# Anemometro8285.net
KiCad netlist of a schematic drawn in EAGLE
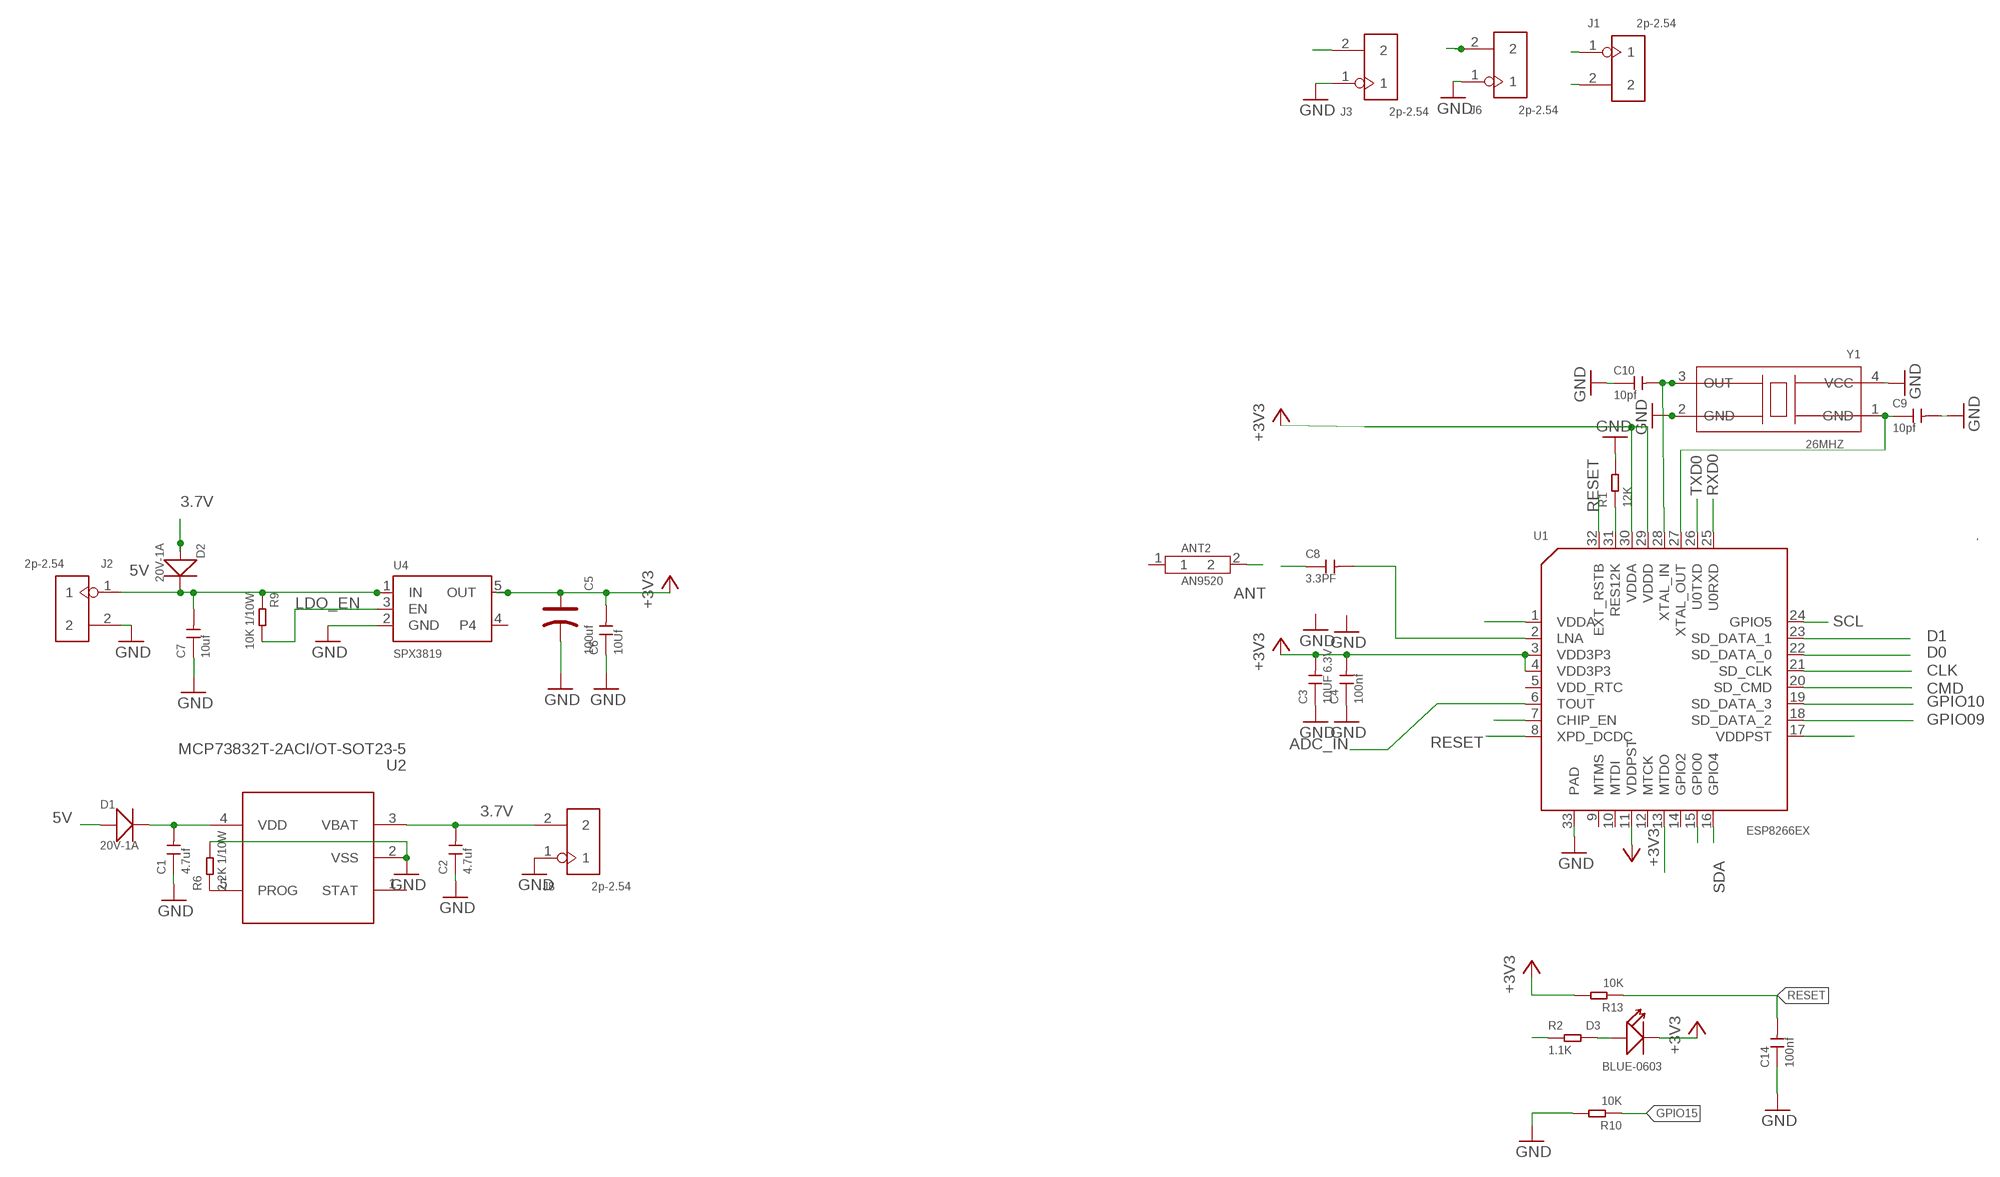
[diagram p0: schematic, sheet 1]

(export (version "E")
  (design (tool "Eeschema 10.0.6"))
  (components
    (comp (ref "ANT2")
      (value "AN9520")
      (footprint "eagle-import:ANT2-SMD-9.5X2X1.2MM")
      (fields (field (name "MPN") "an9520"))
      (libsource (lib "eagle-import") (part "SMD-BUILT-IN-ANTENNA-2.4GHZ(2P-9.5X2.1MM)"))
    )
    (comp (ref "C1")
      (value "4.7uf")
      (footprint "eagle-import:C0603")
      (fields (field (name "MPN") "CC0603KRX5R6BB475"))
      (libsource (lib "eagle-import") (part "CERAMIC-4.7UF-10V-10%-X5R(0603)"))
    )
    (comp (ref "C2")
      (value "4.7uf")
      (footprint "eagle-import:C0603")
      (fields (field (name "MPN") "CC0603KRX5R6BB475"))
      (libsource (lib "eagle-import") (part "CERAMIC-4.7UF-10V-10%-X5R(0603)"))
    )
    (comp (ref "C3")
      (value "10UF 6.3V")
      (footprint "eagle-import:C0603")
      (fields (field (name "MPN") "CC0603MRX5R5BB106"))
      (libsource (lib "eagle-import") (part "CERAMIC-10UF-6.3V-20%-X5R(0603)"))
    )
    (comp (ref "C4")
      (value "100nf")
      (footprint "eagle-import:C0603")
      (fields (field (name "MPN") "CC0603KRX7R9BB104"))
      (libsource (lib "eagle-import") (part "CERAMIC-100NF-50V-10%-X7R(0603)"))
    )
    (comp (ref "C5")
      (value "100uf")
      (footprint "eagle-import:AVX-B")
      (fields (field (name "MPN") "TAJB107M010#NJ"))
      (libsource (lib "eagle-import") (part "TANTALUM-SMD-100UF-10V(AVX-B)"))
    )
    (comp (ref "C6")
      (value "10Uf")
      (footprint "eagle-import:C0603")
      (fields (field (name "MPN") "CC0603KRX7R9BB104"))
      (libsource (lib "eagle-import") (part "CERAMIC-100NF-50V-10%-X7R(0603)"))
    )
    (comp (ref "C7")
      (value "10uf")
      (footprint "eagle-import:C0805")
      (fields (field (name "MPN") "CC0805KKX5R8BB106"))
      (libsource (lib "eagle-import") (part "CERAMIC-10UF-25V-10%-X5R(0805)"))
    )
    (comp (ref "C8")
      (value "3.3PF")
      (footprint "eagle-import:C0603")
      (libsource (lib "eagle-import") (part "CERAMIC-3.3PF-50V-0.25PF-NPO(0603)"))
    )
    (comp (ref "C9")
      (value "10pf")
      (footprint "eagle-import:C0603")
      (libsource (lib "eagle-import") (part "CERAMIC-10PF-50V-5%-NPO(0603)"))
    )
    (comp (ref "C10")
      (value "10pf")
      (footprint "eagle-import:C0603")
      (libsource (lib "eagle-import") (part "CERAMIC-10PF-50V-5%-NPO(0603)"))
    )
    (comp (ref "C14")
      (value "100nf")
      (footprint "eagle-import:C0603")
      (fields (field (name "MPN") "CC0603KRX7R9BB104"))
      (libsource (lib "eagle-import") (part "CERAMIC-100NF-50V-10%-X7R(0603)"))
    )
    (comp (ref "D1")
      (value "20V-1A")
      (footprint "eagle-import:SOD-123")
      (fields (field (name "MPN") "B5819W"))
      (libsource (lib "eagle-import") (part "SMD-DIODE-SCHOTTKY-20V-1A(SOD-123)"))
    )
    (comp (ref "D2")
      (value "20V-1A")
      (footprint "eagle-import:SOD-123")
      (fields (field (name "MPN") "B5819W"))
      (libsource (lib "eagle-import") (part "SMD-DIODE-SCHOTTKY-20V-1A(SOD-123)"))
    )
    (comp (ref "D3")
      (value "BLUE-0603")
      (footprint "eagle-import:LED-0603")
      (fields (field (name "MPN") "19-217-BHC-ZL1M2RY-3T"))
      (libsource (lib "eagle-import") (part "SMD-LED-CLEAR-BLUE(0603)"))
    )
    (comp (ref "J1")
      (value "2p-2.54")
      (footprint "eagle-import:H2-2.54")
      (fields (field (name "MPN") "F185-1102A1BSYA1"))
      (libsource (lib "eagle-import") (part "DIP-BLACK-FEMALE-HEADER-VERT(2P-2.54)"))
    )
    (comp (ref "J2")
      (value "2p-2.54")
      (footprint "eagle-import:H2-2.54")
      (fields (field (name "MPN") "F185-1102A1BSYA1"))
      (libsource (lib "eagle-import") (part "DIP-BLACK-FEMALE-HEADER-VERT(2P-2.54)"))
    )
    (comp (ref "J3")
      (value "2p-2.54")
      (footprint "eagle-import:H2-2.54")
      (fields (field (name "MPN") "P125-1102A0BS116A1"))
      (libsource (lib "eagle-import") (part "DIP-BLACK-MALE-HEADER-VERT(2P-2.54)"))
    )
    (comp (ref "J6")
      (value "2p-2.54")
      (footprint "eagle-import:H2-2.54")
      (fields (field (name "MPN") "P125-1102A0BS116A1"))
      (libsource (lib "eagle-import") (part "DIP-BLACK-MALE-HEADER-VERT(2P-2.54)"))
    )
    (comp (ref "J8")
      (value "2p-2.54")
      (footprint "eagle-import:H2-2.54")
      (fields (field (name "MPN") "F185-1102A1BSYA1"))
      (libsource (lib "eagle-import") (part "DIP-BLACK-FEMALE-HEADER-VERT(2P-2.54)"))
    )
    (comp (ref "R1")
      (value "12K")
      (footprint "eagle-import:R0603")
      (fields (field (name "MPN") "RC0603FR-0712KL"))
      (libsource (lib "eagle-import") (part "SMD-RES-12K-1%-1/10W(0603)"))
    )
    (comp (ref "R2")
      (value "1.1K")
      (footprint "eagle-import:R0603")
      (fields (field (name "MPN") "RC0603JR-071K1L"))
      (libsource (lib "eagle-import") (part "SMD-RES-1.1K-5%-1/10W(0603)"))
    )
    (comp (ref "R6")
      (value "2.2K 1/10W")
      (footprint "eagle-import:R0603")
      (fields (field (name "MPN") "RC0603FR-072K2L"))
      (libsource (lib "eagle-import") (part "SMD-RES-2.2K-1%-1/10W(0603)"))
    )
    (comp (ref "R9")
      (value "10K 1/10W")
      (footprint "eagle-import:R0603")
      (fields (field (name "MPN") "RC0603JR-0710KL"))
      (libsource (lib "eagle-import") (part "SMD-RES-10K-5%-1/10W(0603)"))
    )
    (comp (ref "R10")
      (value "10K")
      (footprint "eagle-import:R0603")
      (fields (field (name "MPN") "RC0603JR-070RL"))
      (libsource (lib "eagle-import") (part "SMD-RES-0R-5%-1/10W(0603)"))
    )
    (comp (ref "R13")
      (value "10K")
      (footprint "eagle-import:R0603")
      (fields (field (name "MPN") "RC0603JR-070RL"))
      (libsource (lib "eagle-import") (part "SMD-RES-0R-5%-1/10W(0603)"))
    )
    (comp (ref "U1")
      (value "ESP8266EX")
      (footprint "eagle-import:QFN32G-0.5-5X5MM")
      (libsource (lib "eagle-import") (part "IC-RF-ESP8266EX(QFN32)"))
    )
    (comp (ref "U2")
      (value "MCP73832T-2ACI/OT-SOT23-5")
      (footprint "eagle-import:SOT-23-5")
      (fields (field (name "MPN") "MCP73832T-2ACI/OT"))
      (libsource (lib "eagle-import") (part "PMIC-MCP73832T-2ACI/OT(SOT23-5)"))
    )
    (comp (ref "U4")
      (value "SPX3819")
      (footprint "eagle-import:SOT23-5")
      (libsource (lib "eagle-import") (part "VREG_SOT23-5"))
    )
    (comp (ref "Y1")
      (value "26MHZ")
      (footprint "eagle-import:X4-SMD-2.5X2.0X0.5MM")
      (fields (field (name "MPN") "7L26002009"))
      (libsource (lib "eagle-import") (part "SMD-CRYSTAL-26MHZ(4P-2.5X2.0X0.8MM)"))
    )
  )
  (nets
    (net (code "1") (name "+3V3") (class "Default")
      (node (ref "C3") (pin "2") (pinfunction "2_2") (pintype "passive"))
      (node (ref "C4") (pin "2") (pinfunction "2_2") (pintype "passive"))
      (node (ref "C5") (pin "+") (pinfunction "+_+") (pintype "passive"))
      (node (ref "C6") (pin "2") (pinfunction "2_2") (pintype "passive"))
      (node (ref "D3") (pin "-") (pinfunction "-_-") (pintype "passive"))
      (node (ref "R13") (pin "2") (pinfunction "2_2") (pintype "passive"))
      (node (ref "U1") (pin "1") (pinfunction "VDDA_1") (pintype "power_in"))
      (node (ref "U1") (pin "11") (pinfunction "VDDPST_11") (pintype "bidirectional"))
      (node (ref "U1") (pin "17") (pinfunction "VDDPST_17") (pintype "bidirectional"))
      (node (ref "U1") (pin "29") (pinfunction "VDDD_29") (pintype "bidirectional"))
      (node (ref "U1") (pin "3") (pinfunction "VDD3P3_3") (pintype "power_in"))
      (node (ref "U1") (pin "30") (pinfunction "VDDA_30") (pintype "bidirectional"))
      (node (ref "U1") (pin "4") (pinfunction "VDD3P3_4") (pintype "power_in"))
      (node (ref "U1") (pin "7") (pinfunction "CHIP_EN_7") (pintype "bidirectional"))
      (node (ref "U4") (pin "5") (pinfunction "OUT_5") (pintype "power_in"))
    )
    (net (code "2") (name "/3.7V") (class "Default")
      (node (ref "C2") (pin "2") (pinfunction "2_2") (pintype "passive"))
      (node (ref "D2") (pin "+") (pinfunction "+_+") (pintype "passive"))
      (node (ref "J8") (pin "2") (pinfunction "2_2") (pintype "bidirectional"))
      (node (ref "U2") (pin "3") (pinfunction "VBAT_3") (pintype "output"))
    )
    (net (code "3") (name "/5V") (class "Default")
      (node (ref "C7") (pin "2") (pinfunction "2_2") (pintype "passive"))
      (node (ref "D1") (pin "+") (pinfunction "+_+") (pintype "passive"))
      (node (ref "D2") (pin "-") (pinfunction "-_-") (pintype "passive"))
      (node (ref "J2") (pin "1") (pinfunction "1_1") (pintype "bidirectional"))
      (node (ref "R9") (pin "1") (pinfunction "1_1") (pintype "passive"))
      (node (ref "U4") (pin "1") (pinfunction "IN_1") (pintype "power_in"))
    )
    (net (code "4") (name "/ADC_IN") (class "Default")
      (node (ref "U1") (pin "6") (pinfunction "TOUT_6") (pintype "output"))
    )
    (net (code "5") (name "/ANT") (class "Default")
      (node (ref "ANT2") (pin "2") (pinfunction "2_2") (pintype "bidirectional"))
      (node (ref "C8") (pin "1") (pinfunction "1_1") (pintype "passive"))
    )
    (net (code "6") (name "/CLK") (class "Default")
      (node (ref "U1") (pin "21") (pinfunction "SD_CLK_21") (pintype "bidirectional"))
    )
    (net (code "7") (name "/CMD") (class "Default")
      (node (ref "U1") (pin "20") (pinfunction "SD_CMD_20") (pintype "bidirectional"))
    )
    (net (code "8") (name "/D0") (class "Default")
      (node (ref "U1") (pin "22") (pinfunction "SD_DATA_0_22") (pintype "bidirectional"))
    )
    (net (code "9") (name "/D1") (class "Default")
      (node (ref "U1") (pin "23") (pinfunction "SD_DATA_1_23") (pintype "bidirectional"))
    )
    (net (code "10") (name "/GPIO0") (class "Default")
      (node (ref "J3") (pin "2") (pinfunction "2_2") (pintype "bidirectional"))
      (node (ref "U1") (pin "15") (pinfunction "GPIO0_15") (pintype "bidirectional"))
    )
    (net (code "11") (name "/GPIO09") (class "Default")
      (node (ref "U1") (pin "18") (pinfunction "SD_DATA_2_18") (pintype "bidirectional"))
    )
    (net (code "12") (name "/GPIO10") (class "Default")
      (node (ref "U1") (pin "19") (pinfunction "SD_DATA_3_19") (pintype "bidirectional"))
    )
    (net (code "13") (name "/LDO_EN") (class "Default")
      (node (ref "R9") (pin "2") (pinfunction "2_2") (pintype "passive"))
      (node (ref "U4") (pin "3") (pinfunction "EN_3") (pintype "input"))
    )
    (net (code "14") (name "/RXD0") (class "Default")
      (node (ref "J1") (pin "2") (pinfunction "2_2") (pintype "bidirectional"))
      (node (ref "U1") (pin "25") (pinfunction "U0RXD_25") (pintype "bidirectional"))
    )
    (net (code "15") (name "/SCL") (class "Default")
      (node (ref "J6") (pin "2") (pinfunction "2_2") (pintype "bidirectional"))
      (node (ref "U1") (pin "24") (pinfunction "GPIO5_24") (pintype "bidirectional"))
    )
    (net (code "16") (name "/SDA") (class "Default")
      (node (ref "U1") (pin "16") (pinfunction "GPIO4_16") (pintype "bidirectional"))
    )
    (net (code "17") (name "/TXD0") (class "Default")
      (node (ref "J1") (pin "1") (pinfunction "1_1") (pintype "bidirectional"))
      (node (ref "R2") (pin "1") (pinfunction "1_1") (pintype "passive"))
      (node (ref "U1") (pin "26") (pinfunction "U0TXD_26") (pintype "bidirectional"))
    )
    (net (code "18") (name "GND") (class "Default")
      (node (ref "C1") (pin "1") (pinfunction "1_1") (pintype "passive"))
      (node (ref "C10") (pin "1") (pinfunction "1_1") (pintype "passive"))
      (node (ref "C14") (pin "1") (pinfunction "1_1") (pintype "passive"))
      (node (ref "C2") (pin "1") (pinfunction "1_1") (pintype "passive"))
      (node (ref "C3") (pin "1") (pinfunction "1_1") (pintype "passive"))
      (node (ref "C4") (pin "1") (pinfunction "1_1") (pintype "passive"))
      (node (ref "C5") (pin "-") (pinfunction "-_-") (pintype "passive"))
      (node (ref "C6") (pin "1") (pinfunction "1_1") (pintype "passive"))
      (node (ref "C7") (pin "1") (pinfunction "1_1") (pintype "passive"))
      (node (ref "C9") (pin "2") (pinfunction "2_2") (pintype "passive"))
      (node (ref "J2") (pin "2") (pinfunction "2_2") (pintype "bidirectional"))
      (node (ref "J3") (pin "1") (pinfunction "1_1") (pintype "bidirectional"))
      (node (ref "J6") (pin "1") (pinfunction "1_1") (pintype "bidirectional"))
      (node (ref "J8") (pin "1") (pinfunction "1_1") (pintype "bidirectional"))
      (node (ref "R1") (pin "2") (pinfunction "2_2") (pintype "passive"))
      (node (ref "R10") (pin "2") (pinfunction "2_2") (pintype "passive"))
      (node (ref "R6") (pin "2") (pinfunction "2_2") (pintype "passive"))
      (node (ref "U1") (pin "33") (pinfunction "PAD_33") (pintype "bidirectional"))
      (node (ref "U2") (pin "2") (pinfunction "VSS_2") (pintype "passive"))
      (node (ref "U4") (pin "2") (pinfunction "GND_2") (pintype "power_in"))
      (node (ref "Y1") (pin "2") (pinfunction "GND_2") (pintype "power_in"))
      (node (ref "Y1") (pin "4") (pinfunction "VCC_4") (pintype "power_in"))
    )
    (net (code "19") (name "GPIO15") (class "Default")
      (node (ref "R10") (pin "1") (pinfunction "1_1") (pintype "passive"))
      (node (ref "U1") (pin "13") (pinfunction "MTDO_13") (pintype "bidirectional"))
    )
    (net (code "20") (name "Net-(D3-Pad+)") (class "Default")
      (node (ref "D3") (pin "+") (pinfunction "+_+") (pintype "passive"))
      (node (ref "R2") (pin "2") (pinfunction "2_2") (pintype "passive"))
    )
    (net (code "21") (name "Net-(U1-LNA)") (class "Default")
      (node (ref "C8") (pin "2") (pinfunction "2_2") (pintype "passive"))
      (node (ref "U1") (pin "2") (pinfunction "LNA_2") (pintype "bidirectional"))
    )
    (net (code "22") (name "Net-(U1-RES12K)") (class "Default")
      (node (ref "R1") (pin "1") (pinfunction "1_1") (pintype "passive"))
      (node (ref "U1") (pin "31") (pinfunction "RES12K_31") (pintype "bidirectional"))
    )
    (net (code "23") (name "Net-(U1-XTAL_IN)") (class "Default")
      (node (ref "C10") (pin "2") (pinfunction "2_2") (pintype "passive"))
      (node (ref "U1") (pin "28") (pinfunction "XTAL_IN_28") (pintype "bidirectional"))
      (node (ref "Y1") (pin "3") (pinfunction "OUT_3") (pintype "output"))
    )
    (net (code "24") (name "Net-(U1-XTAL_OUT)") (class "Default")
      (node (ref "C9") (pin "1") (pinfunction "1_1") (pintype "passive"))
      (node (ref "U1") (pin "27") (pinfunction "XTAL_OUT_27") (pintype "bidirectional"))
      (node (ref "Y1") (pin "1") (pinfunction "GND_1") (pintype "power_in"))
    )
    (net (code "25") (name "Net-(U2-PROG)") (class "Default")
      (node (ref "R6") (pin "1") (pinfunction "1_1") (pintype "passive"))
      (node (ref "U2") (pin "5") (pinfunction "PROG_5") (pintype "input"))
    )
    (net (code "26") (name "Net-(U2-VDD)") (class "Default")
      (node (ref "C1") (pin "2") (pinfunction "2_2") (pintype "passive"))
      (node (ref "D1") (pin "-") (pinfunction "-_-") (pintype "passive"))
      (node (ref "U2") (pin "4") (pinfunction "VDD_4") (pintype "input"))
    )
    (net (code "27") (name "RESET") (class "Default")
      (node (ref "C14") (pin "2") (pinfunction "2_2") (pintype "passive"))
      (node (ref "R13") (pin "1") (pinfunction "1_1") (pintype "passive"))
      (node (ref "U1") (pin "32") (pinfunction "EXT_RSTB_32") (pintype "bidirectional"))
      (node (ref "U1") (pin "8") (pinfunction "XPD_DCDC_8") (pintype "bidirectional"))
    )
    (net (code "28") (name "unconnected-(ANT2-Pad1)") (class "Default")
      (node (ref "ANT2") (pin "1") (pinfunction "1_1") (pintype "bidirectional"))
    )
    (net (code "29") (name "unconnected-(U1-GPIO2-Pad14)") (class "Default")
      (node (ref "U1") (pin "14") (pinfunction "GPIO2_14") (pintype "bidirectional"))
    )
    (net (code "30") (name "unconnected-(U1-MTCK-Pad12)") (class "Default")
      (node (ref "U1") (pin "12") (pinfunction "MTCK_12") (pintype "bidirectional"))
    )
    (net (code "31") (name "unconnected-(U1-MTDI-Pad10)") (class "Default")
      (node (ref "U1") (pin "10") (pinfunction "MTDI_10") (pintype "bidirectional"))
    )
    (net (code "32") (name "unconnected-(U1-MTMS-Pad9)") (class "Default")
      (node (ref "U1") (pin "9") (pinfunction "MTMS_9") (pintype "bidirectional"))
    )
    (net (code "33") (name "unconnected-(U1-VDD_RTC-Pad5)") (class "Default")
      (node (ref "U1") (pin "5") (pinfunction "VDD_RTC_5") (pintype "bidirectional"))
    )
    (net (code "34") (name "unconnected-(U2-STAT-Pad1)") (class "Default")
      (node (ref "U2") (pin "1") (pinfunction "STAT_1") (pintype "output"))
    )
    (net (code "35") (name "unconnected-(U4-P4-Pad4)") (class "Default")
      (node (ref "U4") (pin "4") (pinfunction "P4_4") (pintype "bidirectional"))
    )
  )
)
